# ExtensionConnector.net
KiCad netlist of a schematic drawn in Altium Designer
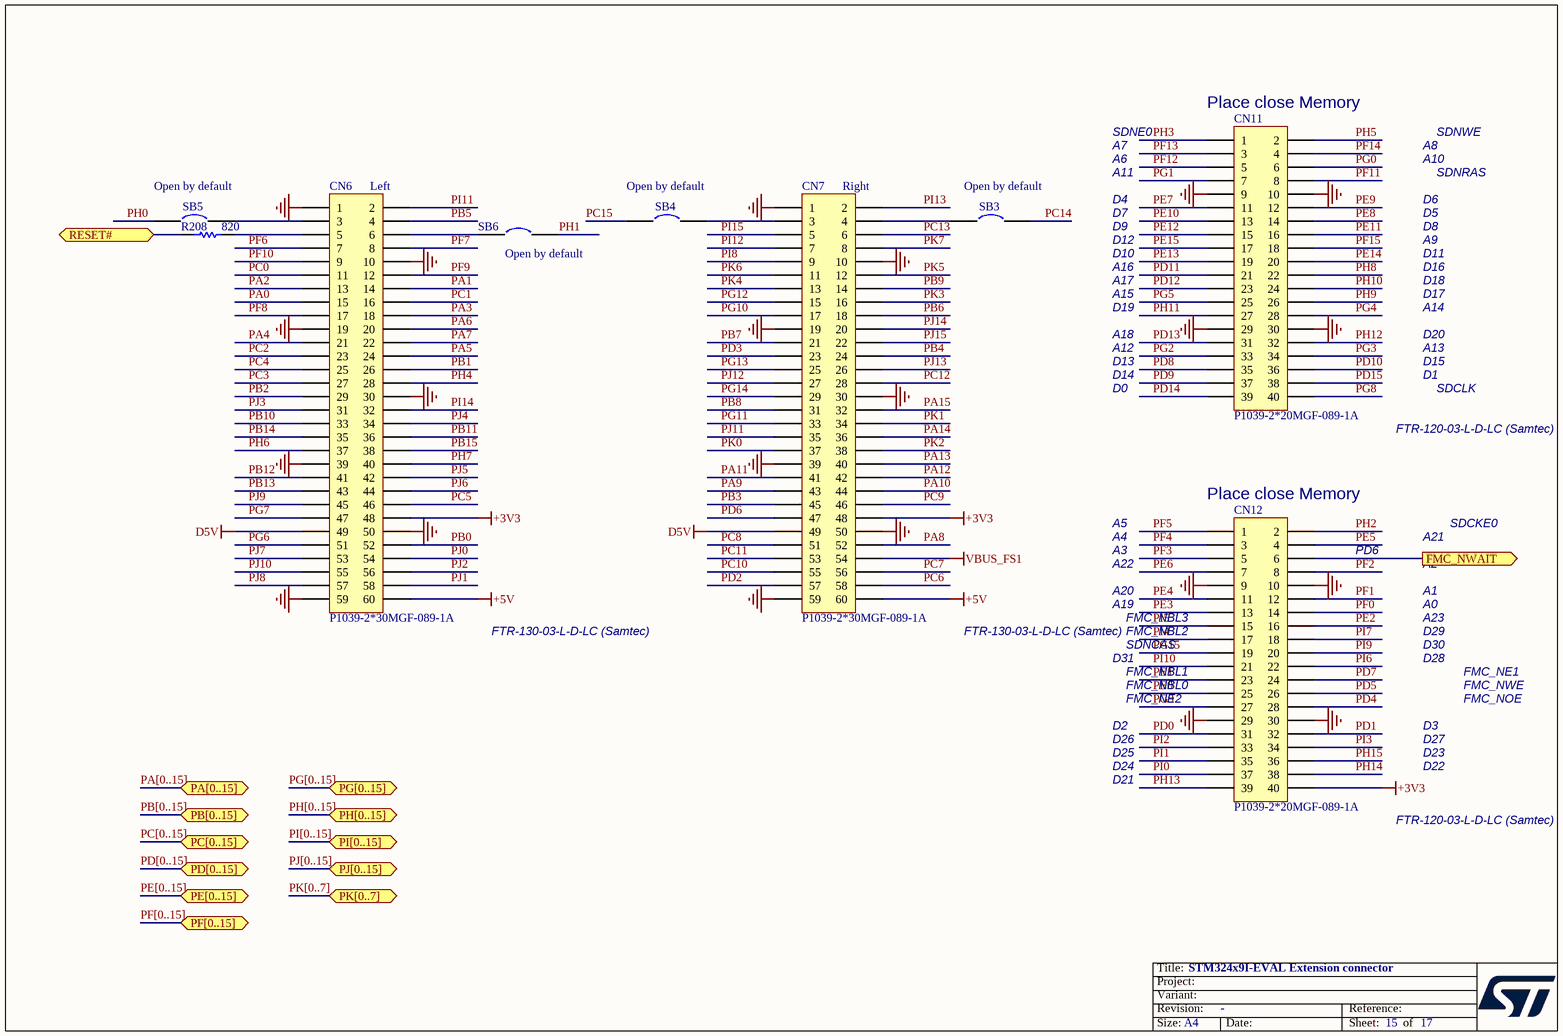
[diagram p0: ExtensionConnector.SchDoc]

(export (version "E")
  (design (tool "Eeschema 10.0.6"))
  (components
    (comp (ref "CN6")
      (value "P1039-2*30MGF-089-1A")
      (footprint "FTR-130-53-L-D-LC")
      (description "Header, 40-Pin, Dual row")
      (fields (field (name "PUBLISHER") "Altium Limited"))
      (libsource (lib "mb1045") (part "FTR-130-53-L-D-LC"))
    )
    (comp (ref "CN7")
      (value "P1039-2*30MGF-089-1A")
      (footprint "FTR-130-53-L-D-LC")
      (description "Header, 40-Pin, Dual row")
      (fields (field (name "PUBLISHER") "Altium Limited"))
      (libsource (lib "mb1045") (part "FTR-130-53-L-D-LC"))
    )
    (comp (ref "CN11")
      (value "P1039-2*20MGF-089-1A")
      (footprint "FTR-120-53-L-D-LC")
      (description "Header, 20-Pin, Dual row")
      (fields (field (name "PUBLISHER") "Altium Limited"))
      (libsource (lib "mb1045") (part "FTR-120-53-L-D-LC"))
    )
    (comp (ref "CN12")
      (value "P1039-2*20MGF-089-1A")
      (footprint "FTR-120-53-L-D-LC")
      (description "Header, 20-Pin, Dual row")
      (fields (field (name "PUBLISHER") "Altium Limited"))
      (libsource (lib "mb1045") (part "FTR-120-53-L-D-LC"))
    )
    (comp (ref "R208")
      (value "820")
      (footprint "0603R")
      (description "Resistor")
      (fields (field (name "PUBLISHER") "Altium Limited"))
      (libsource (lib "Miscellaneous Devices") (part "res1"))
    )
    (comp (ref "SB3")
      (value "~")
      (footprint "JP2_SMD")
      (description "Circuit Breaker")
      (fields (field (name "PUBLISHER") "Altium Limited"))
      (libsource (lib "") (part "Circuit Breaker_1"))
    )
    (comp (ref "SB4")
      (value "~")
      (footprint "JP2_SMD")
      (description "Circuit Breaker")
      (fields (field (name "PUBLISHER") "Altium Limited"))
      (libsource (lib "Miscellaneous Devices") (part "Circuit Breaker"))
    )
    (comp (ref "SB5")
      (value "~")
      (footprint "JP2_SMD")
      (description "Circuit Breaker")
      (fields (field (name "PUBLISHER") "Altium Limited"))
      (libsource (lib "Miscellaneous Devices") (part "Circuit Breaker"))
    )
    (comp (ref "SB6")
      (value "~")
      (footprint "JP2_SMD")
      (description "Circuit Breaker")
      (fields (field (name "PUBLISHER") "Altium Limited"))
      (libsource (lib "") (part "Circuit Breaker_1"))
    )
  )
  (nets
    (net (code "1") (name "+3V3") (class "Default")
      (node (ref "CN12") (pin "40") (pinfunction "40_40") (pintype "passive"))
      (node (ref "CN6") (pin "48") (pinfunction "48_48") (pintype "passive"))
      (node (ref "CN7") (pin "48") (pinfunction "48_48") (pintype "passive"))
    )
    (net (code "2") (name "+5V") (class "Default")
      (node (ref "CN6") (pin "60") (pinfunction "60_60") (pintype "passive"))
      (node (ref "CN7") (pin "60") (pinfunction "60_60") (pintype "passive"))
    )
    (net (code "3") (name "/FMC_NWAIT") (class "Default")
      (node (ref "CN12") (pin "6") (pinfunction "6_6") (pintype "passive"))
    )
    (net (code "4") (name "/PA0") (class "Default")
      (node (ref "CN6") (pin "15") (pinfunction "15_15") (pintype "passive"))
    )
    (net (code "5") (name "/PA1") (class "Default")
      (node (ref "CN6") (pin "14") (pinfunction "14_14") (pintype "passive"))
    )
    (net (code "6") (name "/PA2") (class "Default")
      (node (ref "CN6") (pin "13") (pinfunction "13_13") (pintype "passive"))
    )
    (net (code "7") (name "/PA3") (class "Default")
      (node (ref "CN6") (pin "18") (pinfunction "18_18") (pintype "passive"))
    )
    (net (code "8") (name "/PA4") (class "Default")
      (node (ref "CN6") (pin "21") (pinfunction "21_21") (pintype "passive"))
    )
    (net (code "9") (name "/PA5") (class "Default")
      (node (ref "CN6") (pin "24") (pinfunction "24_24") (pintype "passive"))
    )
    (net (code "10") (name "/PA6") (class "Default")
      (node (ref "CN6") (pin "20") (pinfunction "20_20") (pintype "passive"))
    )
    (net (code "11") (name "/PA7") (class "Default")
      (node (ref "CN6") (pin "22") (pinfunction "22_22") (pintype "passive"))
    )
    (net (code "12") (name "/PA8") (class "Default")
      (node (ref "CN7") (pin "52") (pinfunction "52_52") (pintype "passive"))
    )
    (net (code "13") (name "/PA9") (class "Default")
      (node (ref "CN7") (pin "43") (pinfunction "43_43") (pintype "passive"))
    )
    (net (code "14") (name "/PA10") (class "Default")
      (node (ref "CN7") (pin "44") (pinfunction "44_44") (pintype "passive"))
    )
    (net (code "15") (name "/PA11") (class "Default")
      (node (ref "CN7") (pin "41") (pinfunction "41_41") (pintype "passive"))
    )
    (net (code "16") (name "/PA12") (class "Default")
      (node (ref "CN7") (pin "42") (pinfunction "42_42") (pintype "passive"))
    )
    (net (code "17") (name "/PA13") (class "Default")
      (node (ref "CN7") (pin "40") (pinfunction "40_40") (pintype "passive"))
    )
    (net (code "18") (name "/PA14") (class "Default")
      (node (ref "CN7") (pin "36") (pinfunction "36_36") (pintype "passive"))
    )
    (net (code "19") (name "/PA15") (class "Default")
      (node (ref "CN7") (pin "32") (pinfunction "32_32") (pintype "passive"))
    )
    (net (code "21") (name "/PB0") (class "Default")
      (node (ref "CN6") (pin "52") (pinfunction "52_52") (pintype "passive"))
    )
    (net (code "22") (name "/PB1") (class "Default")
      (node (ref "CN6") (pin "26") (pinfunction "26_26") (pintype "passive"))
    )
    (net (code "23") (name "/PB2") (class "Default")
      (node (ref "CN6") (pin "29") (pinfunction "29_29") (pintype "passive"))
    )
    (net (code "24") (name "/PB3") (class "Default")
      (node (ref "CN7") (pin "45") (pinfunction "45_45") (pintype "passive"))
    )
    (net (code "25") (name "/PB4") (class "Default")
      (node (ref "CN7") (pin "24") (pinfunction "24_24") (pintype "passive"))
    )
    (net (code "26") (name "/PB5") (class "Default")
      (node (ref "CN6") (pin "4") (pinfunction "4_4") (pintype "passive"))
    )
    (net (code "27") (name "/PB6") (class "Default")
      (node (ref "CN7") (pin "18") (pinfunction "18_18") (pintype "passive"))
    )
    (net (code "28") (name "/PB7") (class "Default")
      (node (ref "CN7") (pin "21") (pinfunction "21_21") (pintype "passive"))
    )
    (net (code "29") (name "/PB8") (class "Default")
      (node (ref "CN7") (pin "31") (pinfunction "31_31") (pintype "passive"))
    )
    (net (code "30") (name "/PB9") (class "Default")
      (node (ref "CN7") (pin "14") (pinfunction "14_14") (pintype "passive"))
    )
    (net (code "31") (name "/PB10") (class "Default")
      (node (ref "CN6") (pin "33") (pinfunction "33_33") (pintype "passive"))
    )
    (net (code "32") (name "/PB11") (class "Default")
      (node (ref "CN6") (pin "36") (pinfunction "36_36") (pintype "passive"))
    )
    (net (code "33") (name "/PB12") (class "Default")
      (node (ref "CN6") (pin "41") (pinfunction "41_41") (pintype "passive"))
    )
    (net (code "34") (name "/PB13") (class "Default")
      (node (ref "CN6") (pin "43") (pinfunction "43_43") (pintype "passive"))
    )
    (net (code "35") (name "/PB14") (class "Default")
      (node (ref "CN6") (pin "35") (pinfunction "35_35") (pintype "passive"))
    )
    (net (code "36") (name "/PB15") (class "Default")
      (node (ref "CN6") (pin "38") (pinfunction "38_38") (pintype "passive"))
    )
    (net (code "38") (name "/PC0") (class "Default")
      (node (ref "CN6") (pin "11") (pinfunction "11_11") (pintype "passive"))
    )
    (net (code "39") (name "/PC1") (class "Default")
      (node (ref "CN6") (pin "16") (pinfunction "16_16") (pintype "passive"))
    )
    (net (code "40") (name "/PC2") (class "Default")
      (node (ref "CN6") (pin "23") (pinfunction "23_23") (pintype "passive"))
    )
    (net (code "41") (name "/PC3") (class "Default")
      (node (ref "CN6") (pin "27") (pinfunction "27_27") (pintype "passive"))
    )
    (net (code "42") (name "/PC4") (class "Default")
      (node (ref "CN6") (pin "25") (pinfunction "25_25") (pintype "passive"))
    )
    (net (code "43") (name "/PC5") (class "Default")
      (node (ref "CN6") (pin "46") (pinfunction "46_46") (pintype "passive"))
    )
    (net (code "44") (name "/PC6") (class "Default")
      (node (ref "CN7") (pin "58") (pinfunction "58_58") (pintype "passive"))
    )
    (net (code "45") (name "/PC7") (class "Default")
      (node (ref "CN7") (pin "56") (pinfunction "56_56") (pintype "passive"))
    )
    (net (code "46") (name "/PC8") (class "Default")
      (node (ref "CN7") (pin "51") (pinfunction "51_51") (pintype "passive"))
    )
    (net (code "47") (name "/PC9") (class "Default")
      (node (ref "CN7") (pin "46") (pinfunction "46_46") (pintype "passive"))
    )
    (net (code "48") (name "/PC10") (class "Default")
      (node (ref "CN7") (pin "55") (pinfunction "55_55") (pintype "passive"))
    )
    (net (code "49") (name "/PC11") (class "Default")
      (node (ref "CN7") (pin "53") (pinfunction "53_53") (pintype "passive"))
    )
    (net (code "50") (name "/PC12") (class "Default")
      (node (ref "CN7") (pin "28") (pinfunction "28_28") (pintype "passive"))
    )
    (net (code "51") (name "/PC13") (class "Default")
      (node (ref "CN7") (pin "6") (pinfunction "6_6") (pintype "passive"))
    )
    (net (code "52") (name "/PC14") (class "Default")
      (node (ref "SB3") (pin "1") (pinfunction "1_1") (pintype "passive"))
    )
    (net (code "53") (name "/PC15") (class "Default")
      (node (ref "SB4") (pin "1") (pinfunction "1_1") (pintype "passive"))
    )
    (net (code "55") (name "/PD0") (class "Default")
      (node (ref "CN12") (pin "31") (pinfunction "31_31") (pintype "passive"))
    )
    (net (code "56") (name "/PD1") (class "Default")
      (node (ref "CN12") (pin "32") (pinfunction "32_32") (pintype "passive"))
    )
    (net (code "57") (name "/PD2") (class "Default")
      (node (ref "CN7") (pin "57") (pinfunction "57_57") (pintype "passive"))
    )
    (net (code "58") (name "/PD3") (class "Default")
      (node (ref "CN7") (pin "23") (pinfunction "23_23") (pintype "passive"))
    )
    (net (code "59") (name "/PD4") (class "Default")
      (node (ref "CN12") (pin "28") (pinfunction "28_28") (pintype "passive"))
    )
    (net (code "60") (name "/PD5") (class "Default")
      (node (ref "CN12") (pin "26") (pinfunction "26_26") (pintype "passive"))
    )
    (net (code "61") (name "/PD6") (class "Default")
      (node (ref "CN7") (pin "47") (pinfunction "47_47") (pintype "passive"))
    )
    (net (code "62") (name "/PD7") (class "Default")
      (node (ref "CN12") (pin "24") (pinfunction "24_24") (pintype "passive"))
    )
    (net (code "63") (name "/PD8") (class "Default")
      (node (ref "CN11") (pin "35") (pinfunction "35_35") (pintype "passive"))
    )
    (net (code "64") (name "/PD9") (class "Default")
      (node (ref "CN11") (pin "37") (pinfunction "37_37") (pintype "passive"))
    )
    (net (code "65") (name "/PD10") (class "Default")
      (node (ref "CN11") (pin "36") (pinfunction "36_36") (pintype "passive"))
    )
    (net (code "66") (name "/PD11") (class "Default")
      (node (ref "CN11") (pin "21") (pinfunction "21_21") (pintype "passive"))
    )
    (net (code "67") (name "/PD12") (class "Default")
      (node (ref "CN11") (pin "23") (pinfunction "23_23") (pintype "passive"))
    )
    (net (code "68") (name "/PD13") (class "Default")
      (node (ref "CN11") (pin "31") (pinfunction "31_31") (pintype "passive"))
    )
    (net (code "69") (name "/PD14") (class "Default")
      (node (ref "CN11") (pin "39") (pinfunction "39_39") (pintype "passive"))
    )
    (net (code "70") (name "/PD15") (class "Default")
      (node (ref "CN11") (pin "38") (pinfunction "38_38") (pintype "passive"))
    )
    (net (code "72") (name "/PE0") (class "Default")
      (node (ref "CN12") (pin "25") (pinfunction "25_25") (pintype "passive"))
    )
    (net (code "73") (name "/PE1") (class "Default")
      (node (ref "CN12") (pin "23") (pinfunction "23_23") (pintype "passive"))
    )
    (net (code "74") (name "/PE2") (class "Default")
      (node (ref "CN12") (pin "16") (pinfunction "16_16") (pintype "passive"))
    )
    (net (code "75") (name "/PE3") (class "Default")
      (node (ref "CN12") (pin "13") (pinfunction "13_13") (pintype "passive"))
    )
    (net (code "76") (name "/PE4") (class "Default")
      (node (ref "CN12") (pin "11") (pinfunction "11_11") (pintype "passive"))
    )
    (net (code "77") (name "/PE5") (class "Default")
      (node (ref "CN12") (pin "4") (pinfunction "4_4") (pintype "passive"))
    )
    (net (code "78") (name "/PE6") (class "Default")
      (node (ref "CN12") (pin "7") (pinfunction "7_7") (pintype "passive"))
    )
    (net (code "79") (name "/PE7") (class "Default")
      (node (ref "CN11") (pin "11") (pinfunction "11_11") (pintype "passive"))
    )
    (net (code "80") (name "/PE8") (class "Default")
      (node (ref "CN11") (pin "14") (pinfunction "14_14") (pintype "passive"))
    )
    (net (code "81") (name "/PE9") (class "Default")
      (node (ref "CN11") (pin "12") (pinfunction "12_12") (pintype "passive"))
    )
    (net (code "82") (name "/PE10") (class "Default")
      (node (ref "CN11") (pin "13") (pinfunction "13_13") (pintype "passive"))
    )
    (net (code "83") (name "/PE11") (class "Default")
      (node (ref "CN11") (pin "16") (pinfunction "16_16") (pintype "passive"))
    )
    (net (code "84") (name "/PE12") (class "Default")
      (node (ref "CN11") (pin "15") (pinfunction "15_15") (pintype "passive"))
    )
    (net (code "85") (name "/PE13") (class "Default")
      (node (ref "CN11") (pin "19") (pinfunction "19_19") (pintype "passive"))
    )
    (net (code "86") (name "/PE14") (class "Default")
      (node (ref "CN11") (pin "20") (pinfunction "20_20") (pintype "passive"))
    )
    (net (code "87") (name "/PE15") (class "Default")
      (node (ref "CN11") (pin "17") (pinfunction "17_17") (pintype "passive"))
    )
    (net (code "89") (name "/PF0") (class "Default")
      (node (ref "CN12") (pin "14") (pinfunction "14_14") (pintype "passive"))
    )
    (net (code "90") (name "/PF1") (class "Default")
      (node (ref "CN12") (pin "12") (pinfunction "12_12") (pintype "passive"))
    )
    (net (code "91") (name "/PF2") (class "Default")
      (node (ref "CN12") (pin "8") (pinfunction "8_8") (pintype "passive"))
    )
    (net (code "92") (name "/PF3") (class "Default")
      (node (ref "CN12") (pin "5") (pinfunction "5_5") (pintype "passive"))
    )
    (net (code "93") (name "/PF4") (class "Default")
      (node (ref "CN12") (pin "3") (pinfunction "3_3") (pintype "passive"))
    )
    (net (code "94") (name "/PF5") (class "Default")
      (node (ref "CN12") (pin "1") (pinfunction "1_1") (pintype "passive"))
    )
    (net (code "95") (name "/PF6") (class "Default")
      (node (ref "CN6") (pin "7") (pinfunction "7_7") (pintype "passive"))
    )
    (net (code "96") (name "/PF7") (class "Default")
      (node (ref "CN6") (pin "8") (pinfunction "8_8") (pintype "passive"))
    )
    (net (code "97") (name "/PF8") (class "Default")
      (node (ref "CN6") (pin "17") (pinfunction "17_17") (pintype "passive"))
    )
    (net (code "98") (name "/PF9") (class "Default")
      (node (ref "CN6") (pin "12") (pinfunction "12_12") (pintype "passive"))
    )
    (net (code "99") (name "/PF10") (class "Default")
      (node (ref "CN6") (pin "9") (pinfunction "9_9") (pintype "passive"))
    )
    (net (code "100") (name "/PF11") (class "Default")
      (node (ref "CN11") (pin "8") (pinfunction "8_8") (pintype "passive"))
    )
    (net (code "101") (name "/PF12") (class "Default")
      (node (ref "CN11") (pin "5") (pinfunction "5_5") (pintype "passive"))
    )
    (net (code "102") (name "/PF13") (class "Default")
      (node (ref "CN11") (pin "3") (pinfunction "3_3") (pintype "passive"))
    )
    (net (code "103") (name "/PF14") (class "Default")
      (node (ref "CN11") (pin "4") (pinfunction "4_4") (pintype "passive"))
    )
    (net (code "104") (name "/PF15") (class "Default")
      (node (ref "CN11") (pin "18") (pinfunction "18_18") (pintype "passive"))
    )
    (net (code "106") (name "/PG0") (class "Default")
      (node (ref "CN11") (pin "6") (pinfunction "6_6") (pintype "passive"))
    )
    (net (code "107") (name "/PG1") (class "Default")
      (node (ref "CN11") (pin "7") (pinfunction "7_7") (pintype "passive"))
    )
    (net (code "108") (name "/PG2") (class "Default")
      (node (ref "CN11") (pin "33") (pinfunction "33_33") (pintype "passive"))
    )
    (net (code "109") (name "/PG3") (class "Default")
      (node (ref "CN11") (pin "34") (pinfunction "34_34") (pintype "passive"))
    )
    (net (code "110") (name "/PG4") (class "Default")
      (node (ref "CN11") (pin "28") (pinfunction "28_28") (pintype "passive"))
    )
    (net (code "111") (name "/PG5") (class "Default")
      (node (ref "CN11") (pin "25") (pinfunction "25_25") (pintype "passive"))
    )
    (net (code "112") (name "/PG6") (class "Default")
      (node (ref "CN6") (pin "51") (pinfunction "51_51") (pintype "passive"))
    )
    (net (code "113") (name "/PG7") (class "Default")
      (node (ref "CN6") (pin "47") (pinfunction "47_47") (pintype "passive"))
    )
    (net (code "114") (name "/PG8") (class "Default")
      (node (ref "CN11") (pin "40") (pinfunction "40_40") (pintype "passive"))
    )
    (net (code "115") (name "/PG9") (class "Default")
      (node (ref "CN12") (pin "27") (pinfunction "27_27") (pintype "passive"))
    )
    (net (code "116") (name "/PG10") (class "Default")
      (node (ref "CN7") (pin "17") (pinfunction "17_17") (pintype "passive"))
    )
    (net (code "117") (name "/PG11") (class "Default")
      (node (ref "CN7") (pin "33") (pinfunction "33_33") (pintype "passive"))
    )
    (net (code "118") (name "/PG12") (class "Default")
      (node (ref "CN7") (pin "15") (pinfunction "15_15") (pintype "passive"))
    )
    (net (code "119") (name "/PG13") (class "Default")
      (node (ref "CN7") (pin "25") (pinfunction "25_25") (pintype "passive"))
    )
    (net (code "120") (name "/PG14") (class "Default")
      (node (ref "CN7") (pin "29") (pinfunction "29_29") (pintype "passive"))
    )
    (net (code "121") (name "/PG15") (class "Default")
      (node (ref "CN12") (pin "19") (pinfunction "19_19") (pintype "passive"))
    )
    (net (code "123") (name "/PH0") (class "Default")
      (node (ref "SB5") (pin "1") (pinfunction "1_1") (pintype "passive"))
    )
    (net (code "124") (name "/PH1") (class "Default")
      (node (ref "SB6") (pin "1") (pinfunction "1_1") (pintype "passive"))
    )
    (net (code "125") (name "/PH2") (class "Default")
      (node (ref "CN12") (pin "2") (pinfunction "2_2") (pintype "passive"))
    )
    (net (code "126") (name "/PH3") (class "Default")
      (node (ref "CN11") (pin "1") (pinfunction "1_1") (pintype "passive"))
    )
    (net (code "127") (name "/PH4") (class "Default")
      (node (ref "CN6") (pin "28") (pinfunction "28_28") (pintype "passive"))
    )
    (net (code "128") (name "/PH5") (class "Default")
      (node (ref "CN11") (pin "2") (pinfunction "2_2") (pintype "passive"))
    )
    (net (code "129") (name "/PH6") (class "Default")
      (node (ref "CN6") (pin "37") (pinfunction "37_37") (pintype "passive"))
    )
    (net (code "130") (name "/PH7") (class "Default")
      (node (ref "CN6") (pin "40") (pinfunction "40_40") (pintype "passive"))
    )
    (net (code "131") (name "/PH8") (class "Default")
      (node (ref "CN11") (pin "22") (pinfunction "22_22") (pintype "passive"))
    )
    (net (code "132") (name "/PH9") (class "Default")
      (node (ref "CN11") (pin "26") (pinfunction "26_26") (pintype "passive"))
    )
    (net (code "133") (name "/PH10") (class "Default")
      (node (ref "CN11") (pin "24") (pinfunction "24_24") (pintype "passive"))
    )
    (net (code "134") (name "/PH11") (class "Default")
      (node (ref "CN11") (pin "27") (pinfunction "27_27") (pintype "passive"))
    )
    (net (code "135") (name "/PH12") (class "Default")
      (node (ref "CN11") (pin "32") (pinfunction "32_32") (pintype "passive"))
    )
    (net (code "136") (name "/PH13") (class "Default")
      (node (ref "CN12") (pin "39") (pinfunction "39_39") (pintype "passive"))
    )
    (net (code "137") (name "/PH14") (class "Default")
      (node (ref "CN12") (pin "38") (pinfunction "38_38") (pintype "passive"))
    )
    (net (code "138") (name "/PH15") (class "Default")
      (node (ref "CN12") (pin "36") (pinfunction "36_36") (pintype "passive"))
    )
    (net (code "140") (name "/PI0") (class "Default")
      (node (ref "CN12") (pin "37") (pinfunction "37_37") (pintype "passive"))
    )
    (net (code "141") (name "/PI1") (class "Default")
      (node (ref "CN12") (pin "35") (pinfunction "35_35") (pintype "passive"))
    )
    (net (code "142") (name "/PI2") (class "Default")
      (node (ref "CN12") (pin "33") (pinfunction "33_33") (pintype "passive"))
    )
    (net (code "143") (name "/PI3") (class "Default")
      (node (ref "CN12") (pin "34") (pinfunction "34_34") (pintype "passive"))
    )
    (net (code "144") (name "/PI4") (class "Default")
      (node (ref "CN12") (pin "17") (pinfunction "17_17") (pintype "passive"))
    )
    (net (code "145") (name "/PI5") (class "Default")
      (node (ref "CN12") (pin "15") (pinfunction "15_15") (pintype "passive"))
    )
    (net (code "146") (name "/PI6") (class "Default")
      (node (ref "CN12") (pin "22") (pinfunction "22_22") (pintype "passive"))
    )
    (net (code "147") (name "/PI7") (class "Default")
      (node (ref "CN12") (pin "18") (pinfunction "18_18") (pintype "passive"))
    )
    (net (code "148") (name "/PI8") (class "Default")
      (node (ref "CN7") (pin "9") (pinfunction "9_9") (pintype "passive"))
    )
    (net (code "149") (name "/PI9") (class "Default")
      (node (ref "CN12") (pin "20") (pinfunction "20_20") (pintype "passive"))
    )
    (net (code "150") (name "/PI10") (class "Default")
      (node (ref "CN12") (pin "21") (pinfunction "21_21") (pintype "passive"))
    )
    (net (code "151") (name "/PI11") (class "Default")
      (node (ref "CN6") (pin "2") (pinfunction "2_2") (pintype "passive"))
    )
    (net (code "152") (name "/PI12") (class "Default")
      (node (ref "CN7") (pin "7") (pinfunction "7_7") (pintype "passive"))
    )
    (net (code "153") (name "/PI13") (class "Default")
      (node (ref "CN7") (pin "2") (pinfunction "2_2") (pintype "passive"))
    )
    (net (code "154") (name "/PI14") (class "Default")
      (node (ref "CN6") (pin "32") (pinfunction "32_32") (pintype "passive"))
    )
    (net (code "155") (name "/PI15") (class "Default")
      (node (ref "CN7") (pin "5") (pinfunction "5_5") (pintype "passive"))
    )
    (net (code "157") (name "/PJ0") (class "Default")
      (node (ref "CN6") (pin "54") (pinfunction "54_54") (pintype "passive"))
    )
    (net (code "158") (name "/PJ1") (class "Default")
      (node (ref "CN6") (pin "58") (pinfunction "58_58") (pintype "passive"))
    )
    (net (code "159") (name "/PJ2") (class "Default")
      (node (ref "CN6") (pin "56") (pinfunction "56_56") (pintype "passive"))
    )
    (net (code "160") (name "/PJ3") (class "Default")
      (node (ref "CN6") (pin "31") (pinfunction "31_31") (pintype "passive"))
    )
    (net (code "161") (name "/PJ4") (class "Default")
      (node (ref "CN6") (pin "34") (pinfunction "34_34") (pintype "passive"))
    )
    (net (code "162") (name "/PJ5") (class "Default")
      (node (ref "CN6") (pin "42") (pinfunction "42_42") (pintype "passive"))
    )
    (net (code "163") (name "/PJ6") (class "Default")
      (node (ref "CN6") (pin "44") (pinfunction "44_44") (pintype "passive"))
    )
    (net (code "164") (name "/PJ7") (class "Default")
      (node (ref "CN6") (pin "53") (pinfunction "53_53") (pintype "passive"))
    )
    (net (code "165") (name "/PJ8") (class "Default")
      (node (ref "CN6") (pin "57") (pinfunction "57_57") (pintype "passive"))
    )
    (net (code "166") (name "/PJ9") (class "Default")
      (node (ref "CN6") (pin "45") (pinfunction "45_45") (pintype "passive"))
    )
    (net (code "167") (name "/PJ10") (class "Default")
      (node (ref "CN6") (pin "55") (pinfunction "55_55") (pintype "passive"))
    )
    (net (code "168") (name "/PJ11") (class "Default")
      (node (ref "CN7") (pin "35") (pinfunction "35_35") (pintype "passive"))
    )
    (net (code "169") (name "/PJ12") (class "Default")
      (node (ref "CN7") (pin "27") (pinfunction "27_27") (pintype "passive"))
    )
    (net (code "170") (name "/PJ13") (class "Default")
      (node (ref "CN7") (pin "26") (pinfunction "26_26") (pintype "passive"))
    )
    (net (code "171") (name "/PJ14") (class "Default")
      (node (ref "CN7") (pin "20") (pinfunction "20_20") (pintype "passive"))
    )
    (net (code "172") (name "/PJ15") (class "Default")
      (node (ref "CN7") (pin "22") (pinfunction "22_22") (pintype "passive"))
    )
    (net (code "174") (name "/PK0") (class "Default")
      (node (ref "CN7") (pin "37") (pinfunction "37_37") (pintype "passive"))
    )
    (net (code "175") (name "/PK1") (class "Default")
      (node (ref "CN7") (pin "34") (pinfunction "34_34") (pintype "passive"))
    )
    (net (code "176") (name "/PK2") (class "Default")
      (node (ref "CN7") (pin "38") (pinfunction "38_38") (pintype "passive"))
    )
    (net (code "177") (name "/PK3") (class "Default")
      (node (ref "CN7") (pin "16") (pinfunction "16_16") (pintype "passive"))
    )
    (net (code "178") (name "/PK4") (class "Default")
      (node (ref "CN7") (pin "13") (pinfunction "13_13") (pintype "passive"))
    )
    (net (code "179") (name "/PK5") (class "Default")
      (node (ref "CN7") (pin "12") (pinfunction "12_12") (pintype "passive"))
    )
    (net (code "180") (name "/PK6") (class "Default")
      (node (ref "CN7") (pin "11") (pinfunction "11_11") (pintype "passive"))
    )
    (net (code "181") (name "/PK7") (class "Default")
      (node (ref "CN7") (pin "8") (pinfunction "8_8") (pintype "passive"))
    )
    (net (code "183") (name "/RESET#") (class "Default")
      (node (ref "R208") (pin "1") (pinfunction "1_1") (pintype "passive"))
    )
    (net (code "184") (name "D5V") (class "Default")
      (node (ref "CN6") (pin "49") (pinfunction "49_49") (pintype "passive"))
      (node (ref "CN7") (pin "49") (pinfunction "49_49") (pintype "passive"))
    )
    (net (code "185") (name "GND") (class "Default")
      (node (ref "CN11") (pin "10") (pinfunction "10_10") (pintype "passive"))
      (node (ref "CN11") (pin "29") (pinfunction "29_29") (pintype "passive"))
      (node (ref "CN11") (pin "30") (pinfunction "30_30") (pintype "passive"))
      (node (ref "CN11") (pin "9") (pinfunction "9_9") (pintype "passive"))
      (node (ref "CN12") (pin "10") (pinfunction "10_10") (pintype "passive"))
      (node (ref "CN12") (pin "29") (pinfunction "29_29") (pintype "passive"))
      (node (ref "CN12") (pin "30") (pinfunction "30_30") (pintype "passive"))
      (node (ref "CN12") (pin "9") (pinfunction "9_9") (pintype "passive"))
      (node (ref "CN6") (pin "1") (pinfunction "1_1") (pintype "passive"))
      (node (ref "CN6") (pin "10") (pinfunction "10_10") (pintype "passive"))
      (node (ref "CN6") (pin "19") (pinfunction "19_19") (pintype "passive"))
      (node (ref "CN6") (pin "30") (pinfunction "30_30") (pintype "passive"))
      (node (ref "CN6") (pin "39") (pinfunction "39_39") (pintype "passive"))
      (node (ref "CN6") (pin "50") (pinfunction "50_50") (pintype "passive"))
      (node (ref "CN6") (pin "59") (pinfunction "59_59") (pintype "passive"))
      (node (ref "CN7") (pin "1") (pinfunction "1_1") (pintype "passive"))
      (node (ref "CN7") (pin "10") (pinfunction "10_10") (pintype "passive"))
      (node (ref "CN7") (pin "19") (pinfunction "19_19") (pintype "passive"))
      (node (ref "CN7") (pin "30") (pinfunction "30_30") (pintype "passive"))
      (node (ref "CN7") (pin "39") (pinfunction "39_39") (pintype "passive"))
      (node (ref "CN7") (pin "50") (pinfunction "50_50") (pintype "passive"))
      (node (ref "CN7") (pin "59") (pinfunction "59_59") (pintype "passive"))
    )
    (net (code "186") (name "Net-(CN6-Pad3)") (class "Default")
      (node (ref "CN6") (pin "3") (pinfunction "3_3") (pintype "passive"))
      (node (ref "SB5") (pin "2") (pinfunction "2_2") (pintype "passive"))
    )
    (net (code "187") (name "Net-(CN6-Pad5)") (class "Default")
      (node (ref "CN6") (pin "5") (pinfunction "5_5") (pintype "passive"))
      (node (ref "R208") (pin "2") (pinfunction "2_2") (pintype "passive"))
    )
    (net (code "188") (name "Net-(CN6-Pad6)") (class "Default")
      (node (ref "CN6") (pin "6") (pinfunction "6_6") (pintype "passive"))
      (node (ref "SB6") (pin "2") (pinfunction "2_2") (pintype "passive"))
    )
    (net (code "189") (name "Net-(CN7-Pad3)") (class "Default")
      (node (ref "CN7") (pin "3") (pinfunction "3_3") (pintype "passive"))
      (node (ref "SB4") (pin "2") (pinfunction "2_2") (pintype "passive"))
    )
    (net (code "190") (name "Net-(CN7-Pad4)") (class "Default")
      (node (ref "CN7") (pin "4") (pinfunction "4_4") (pintype "passive"))
      (node (ref "SB3") (pin "2") (pinfunction "2_2") (pintype "passive"))
    )
    (net (code "191") (name "VBUS_FS1") (class "Default")
      (node (ref "CN7") (pin "54") (pinfunction "54_54") (pintype "passive"))
    )
  )
)
